# 310_usb_memory.net
KiCad netlist of a schematic drawn in EAGLE
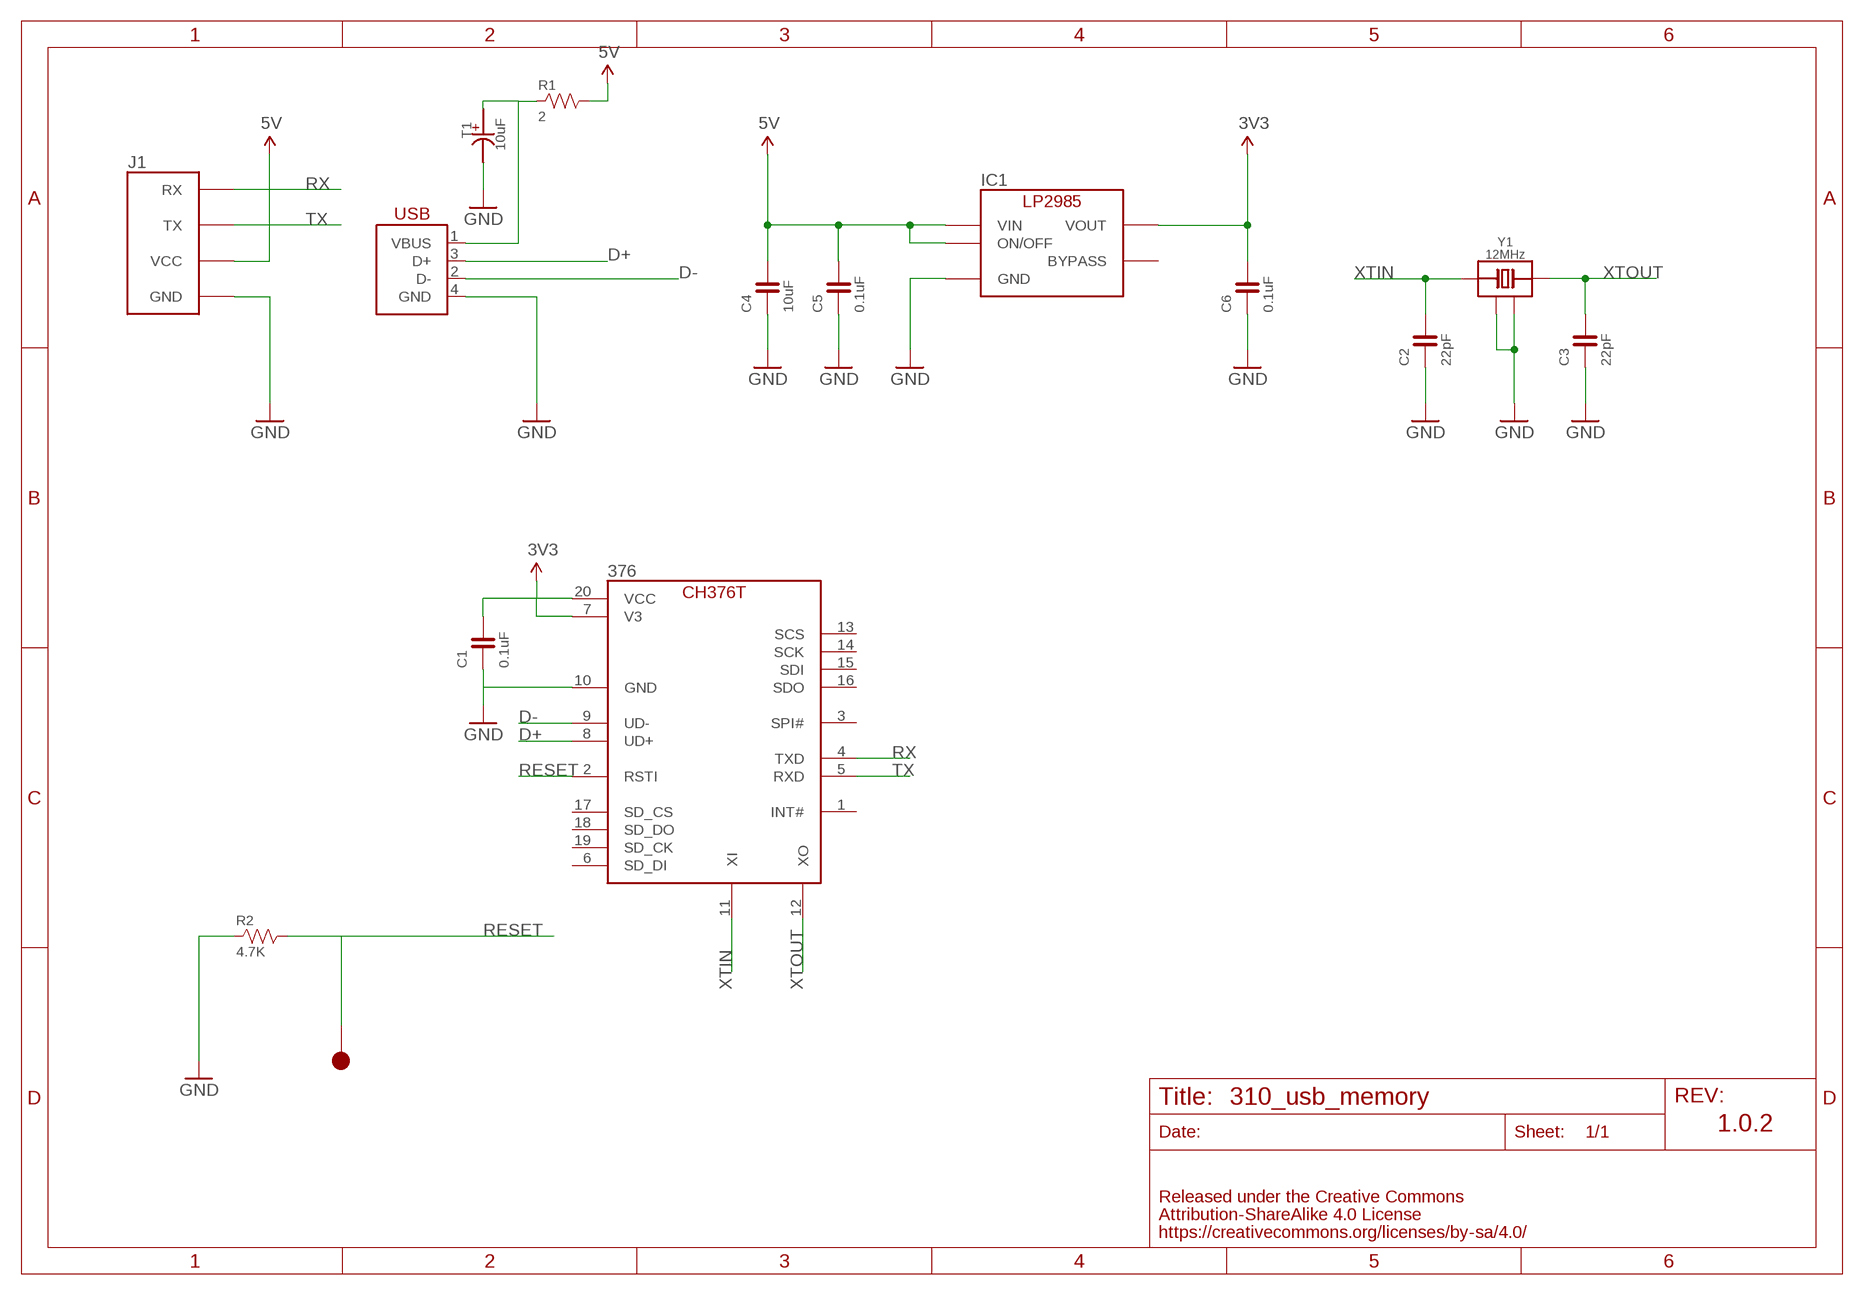
[diagram p0: schematic, sheet 1]

(export (version "E")
  (design (tool "Eeschema 10.0.6"))
  (components
    (comp (ref "376")
      (value "CH376T")
      (footprint "eagle-import:SSOP-20")
      (libsource (lib "eagle-import") (part "CH376T"))
    )
    (comp (ref "C1")
      (value "0.1uF")
      (footprint "eagle-import:0603-NARROW")
      (libsource (lib "eagle-import") (part "CAPACITOR-0603_NARROW"))
    )
    (comp (ref "C2")
      (value "22pF")
      (footprint "eagle-import:0603-NARROW")
      (libsource (lib "eagle-import") (part "CAPACITOR-0603_NARROW"))
    )
    (comp (ref "C3")
      (value "22pF")
      (footprint "eagle-import:0603-NARROW")
      (libsource (lib "eagle-import") (part "CAPACITOR-0603_NARROW"))
    )
    (comp (ref "C4")
      (value "10uF")
      (footprint "eagle-import:0603-NARROW")
      (libsource (lib "eagle-import") (part "CAPACITOR-0603_NARROW"))
    )
    (comp (ref "C5")
      (value "0.1uF")
      (footprint "eagle-import:0603-NARROW")
      (libsource (lib "eagle-import") (part "CAPACITOR-0603_NARROW"))
    )
    (comp (ref "C6")
      (value "0.1uF")
      (footprint "eagle-import:0603-NARROW")
      (libsource (lib "eagle-import") (part "CAPACITOR-0603_NARROW"))
    )
    (comp (ref "IC1")
      (value "LP2985-33DBV")
      (footprint "eagle-import:SOT-23-5")
      (libsource (lib "eagle-import") (part "LP2985-33DBV"))
    )
    (comp (ref "J1")
      (value "FABO_BRICK_SERIAL")
      (footprint "eagle-import:FABO_BRICK_SERIAL")
      (libsource (lib "eagle-import") (part "FABO_BRICK_SERIAL"))
    )
    (comp (ref "R1")
      (value "2")
      (footprint "eagle-import:0603")
      (libsource (lib "eagle-import") (part "RESISTOR-0603"))
    )
    (comp (ref "R2")
      (value "4.7K")
      (footprint "eagle-import:0603")
      (libsource (lib "eagle-import") (part "RESISTOR-0603"))
    )
    (comp (ref "T1")
      (value "10uF")
      (footprint "eagle-import:1206-TANTULM")
      (libsource (lib "eagle-import") (part "CAPACITOR-TANTULM"))
    )
    (comp (ref "TP1")
      (value "TP-15")
      (footprint "eagle-import:TP-15")
      (libsource (lib "eagle-import") (part "TP-15"))
    )
    (comp (ref "USB1")
      (value "USB-B_PTH")
      (footprint "eagle-import:USB-4AF103BS")
      (libsource (lib "eagle-import") (part "USB-B_PTH"))
    )
    (comp (ref "Y1")
      (value "12MHz")
      (footprint "eagle-import:ECS-12MHZ")
      (libsource (lib "eagle-import") (part "CRYSTAL-ECS-120-12-33Q"))
    )
  )
  (nets
    (net (code "1") (name "/D+") (class "Default")
      (node (ref "376") (pin "8") (pinfunction "UD+_8") (pintype "bidirectional"))
      (node (ref "USB1") (pin "3") (pinfunction "D+_3") (pintype "bidirectional"))
    )
    (net (code "2") (name "/D-") (class "Default")
      (node (ref "376") (pin "9") (pinfunction "UD-_9") (pintype "bidirectional"))
      (node (ref "USB1") (pin "2") (pinfunction "D-_2") (pintype "bidirectional"))
    )
    (net (code "3") (name "/RESET") (class "Default")
      (node (ref "376") (pin "2") (pinfunction "RSTI_2") (pintype "bidirectional"))
      (node (ref "R2") (pin "2") (pinfunction "2_2") (pintype "bidirectional"))
      (node (ref "TP1") (pin "1") (pinfunction "1_1") (pintype "bidirectional"))
    )
    (net (code "4") (name "/RX") (class "Default")
      (node (ref "376") (pin "4") (pinfunction "TXD_4") (pintype "bidirectional"))
      (node (ref "J1") (pin "RX") (pinfunction "RX_RX") (pintype "bidirectional"))
    )
    (net (code "5") (name "/TX") (class "Default")
      (node (ref "376") (pin "5") (pinfunction "RXD_5") (pintype "bidirectional"))
      (node (ref "J1") (pin "TX") (pinfunction "TX_TX") (pintype "bidirectional"))
    )
    (net (code "6") (name "/XTIN") (class "Default")
      (node (ref "376") (pin "11") (pinfunction "XI_11") (pintype "bidirectional"))
      (node (ref "C2") (pin "2") (pinfunction "2_2") (pintype "passive"))
      (node (ref "Y1") (pin "1") (pinfunction "IO_1") (pintype "bidirectional"))
    )
    (net (code "7") (name "/XTOUT") (class "Default")
      (node (ref "376") (pin "12") (pinfunction "XO_12") (pintype "bidirectional"))
      (node (ref "C3") (pin "2") (pinfunction "2_2") (pintype "passive"))
      (node (ref "Y1") (pin "3") (pinfunction "IO_3") (pintype "bidirectional"))
    )
    (net (code "8") (name "3V3") (class "Default")
      (node (ref "376") (pin "20") (pinfunction "VCC_20") (pintype "bidirectional"))
      (node (ref "376") (pin "7") (pinfunction "V3_7") (pintype "bidirectional"))
      (node (ref "C1") (pin "2") (pinfunction "2_2") (pintype "passive"))
      (node (ref "C6") (pin "2") (pinfunction "2_2") (pintype "passive"))
      (node (ref "IC1") (pin "5") (pinfunction "VOUT_5") (pintype "output"))
    )
    (net (code "9") (name "5V") (class "Default")
      (node (ref "C4") (pin "2") (pinfunction "2_2") (pintype "passive"))
      (node (ref "C5") (pin "2") (pinfunction "2_2") (pintype "passive"))
      (node (ref "IC1") (pin "1") (pinfunction "VIN_1") (pintype "input"))
      (node (ref "IC1") (pin "3") (pinfunction "ON/OFF_3") (pintype "input"))
      (node (ref "J1") (pin "VCC") (pinfunction "VCC_VCC") (pintype "bidirectional"))
      (node (ref "R1") (pin "2") (pinfunction "2_2") (pintype "bidirectional"))
    )
    (net (code "10") (name "GND") (class "Default")
      (node (ref "376") (pin "10") (pinfunction "GND_10") (pintype "bidirectional"))
      (node (ref "C1") (pin "1") (pinfunction "1_1") (pintype "passive"))
      (node (ref "C2") (pin "1") (pinfunction "1_1") (pintype "passive"))
      (node (ref "C3") (pin "1") (pinfunction "1_1") (pintype "passive"))
      (node (ref "C4") (pin "1") (pinfunction "1_1") (pintype "passive"))
      (node (ref "C5") (pin "1") (pinfunction "1_1") (pintype "passive"))
      (node (ref "C6") (pin "1") (pinfunction "1_1") (pintype "passive"))
      (node (ref "IC1") (pin "2") (pinfunction "GND_2") (pintype "power_in"))
      (node (ref "J1") (pin "GND") (pinfunction "GND_GND") (pintype "bidirectional"))
      (node (ref "R2") (pin "1") (pinfunction "1_1") (pintype "bidirectional"))
      (node (ref "T1") (pin "-") (pinfunction "-_-") (pintype "passive"))
      (node (ref "USB1") (pin "4") (pinfunction "GND_4") (pintype "bidirectional"))
      (node (ref "Y1") (pin "2") (pinfunction "GND_2") (pintype "bidirectional"))
      (node (ref "Y1") (pin "4") (pinfunction "GND_4") (pintype "bidirectional"))
    )
    (net (code "11") (name "Net-(USB1-VBUS)") (class "Default")
      (node (ref "R1") (pin "1") (pinfunction "1_1") (pintype "bidirectional"))
      (node (ref "T1") (pin "+") (pinfunction "+_+") (pintype "passive"))
      (node (ref "USB1") (pin "1") (pinfunction "VBUS_1") (pintype "bidirectional"))
    )
    (net (code "12") (name "unconnected-(376-INT#-Pad1)") (class "Default")
      (node (ref "376") (pin "1") (pinfunction "INT#_1") (pintype "bidirectional"))
    )
    (net (code "13") (name "unconnected-(376-SCK-Pad14)") (class "Default")
      (node (ref "376") (pin "14") (pinfunction "SCK_14") (pintype "bidirectional"))
    )
    (net (code "14") (name "unconnected-(376-SCS-Pad13)") (class "Default")
      (node (ref "376") (pin "13") (pinfunction "SCS_13") (pintype "bidirectional"))
    )
    (net (code "15") (name "unconnected-(376-SDI-Pad15)") (class "Default")
      (node (ref "376") (pin "15") (pinfunction "SDI_15") (pintype "bidirectional"))
    )
    (net (code "16") (name "unconnected-(376-SDO-Pad16)") (class "Default")
      (node (ref "376") (pin "16") (pinfunction "SDO_16") (pintype "bidirectional"))
    )
    (net (code "17") (name "unconnected-(376-SD_CK-Pad19)") (class "Default")
      (node (ref "376") (pin "19") (pinfunction "SD_CK_19") (pintype "bidirectional"))
    )
    (net (code "18") (name "unconnected-(376-SD_CS-Pad17)") (class "Default")
      (node (ref "376") (pin "17") (pinfunction "SD_CS_17") (pintype "bidirectional"))
    )
    (net (code "19") (name "unconnected-(376-SD_DI-Pad6)") (class "Default")
      (node (ref "376") (pin "6") (pinfunction "SD_DI_6") (pintype "bidirectional"))
    )
    (net (code "20") (name "unconnected-(376-SD_DO-Pad18)") (class "Default")
      (node (ref "376") (pin "18") (pinfunction "SD_DO_18") (pintype "bidirectional"))
    )
    (net (code "21") (name "unconnected-(376-SPI#-Pad3)") (class "Default")
      (node (ref "376") (pin "3") (pinfunction "SPI#_3") (pintype "bidirectional"))
    )
    (net (code "22") (name "unconnected-(IC1-BYPASS-Pad4)") (class "Default")
      (node (ref "IC1") (pin "4") (pinfunction "BYPASS_4") (pintype "bidirectional"))
    )
  )
)
